# LCD.net
KiCad netlist of a schematic drawn in Altium Designer
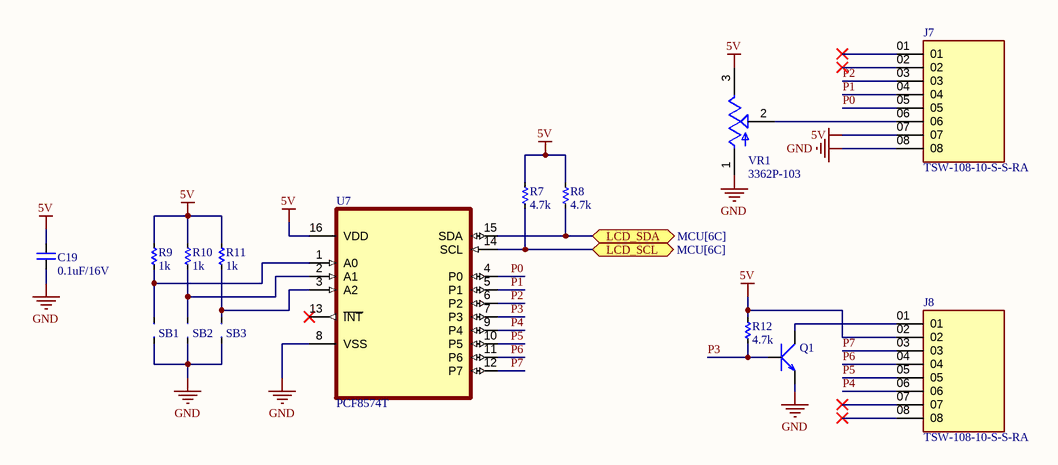
[diagram p0: LCD.SchDoc]

(export (version "E")
  (design (tool "Eeschema 10.0.6"))
  (components
    (comp (ref "C19")
      (value "0.1uF/16V")
      (footprint "CAP_C_1608X80")
      (description "CAP_Chip")
      (libsource (lib "BTL_SCHLIB") (part "CAP_SMD"))
    )
    (comp (ref "J7")
      (value "TSW-108-10-S-S-RA")
      (footprint "SAMTEC_TSW-108-10-S-S-RA")
      (description "Connector Header Through Hole, Right Angle 8 position 0.100 (2.54mm)")
      (fields (field (name "MF") "Samtec"))
      (libsource (lib "BTL_SCHLIB") (part "TSW-108-10-S-S-RA"))
    )
    (comp (ref "J8")
      (value "TSW-108-10-S-S-RA")
      (footprint "SAMTEC_TSW-108-10-S-S-RA")
      (description "Connector Header Through Hole, Right Angle 8 position 0.100 (2.54mm)")
      (fields (field (name "MF") "Samtec"))
      (libsource (lib "BTL_SCHLIB") (part "TSW-108-10-S-S-RA"))
    )
    (comp (ref "Q1")
      (value "SMD-TRANSISTORS-NPN-25V-500MW(SOT-23)")
      (footprint "SOT-23")
      (description "Bipolar (BJT) Transistor NPN 25 V 500 mA 150MHz 300 mW Surface Mount SOT-23")
      (fields (field (name "MF") "UMW") (field (name "MP") "S8050"))
      (libsource (lib "BTL_SCHLIB") (part "SMD-TRANSISTORS-NPN-25V-500MW(SOT-23)"))
    )
    (comp (ref "R7")
      (value "4.7k")
      (footprint "RES_C_1608X60")
      (description "RES")
      (libsource (lib "BTL_SCHLIB") (part "RES_SMD"))
    )
    (comp (ref "R8")
      (value "4.7k")
      (footprint "RES_C_1608X60")
      (description "RES")
      (libsource (lib "BTL_SCHLIB") (part "RES_SMD"))
    )
    (comp (ref "R9")
      (value "1k")
      (footprint "RES_C_1608X60")
      (description "RES")
      (libsource (lib "BTL_SCHLIB") (part "RES_SMD"))
    )
    (comp (ref "R10")
      (value "1k")
      (footprint "RES_C_1608X60")
      (description "RES")
      (libsource (lib "BTL_SCHLIB") (part "RES_SMD"))
    )
    (comp (ref "R11")
      (value "1k")
      (footprint "RES_C_1608X60")
      (description "RES")
      (libsource (lib "BTL_SCHLIB") (part "RES_SMD"))
    )
    (comp (ref "R12")
      (value "4.7k")
      (footprint "RES_C_1608X60")
      (description "RES")
      (libsource (lib "BTL_SCHLIB") (part "RES_SMD"))
    )
    (comp (ref "SB1")
      (value "JUMPER")
      (footprint "JUMPER_1608")
      (libsource (lib "BTL_SCHLIB") (part "JUMPER"))
    )
    (comp (ref "SB2")
      (value "JUMPER")
      (footprint "JUMPER_1608")
      (libsource (lib "BTL_SCHLIB") (part "JUMPER"))
    )
    (comp (ref "SB3")
      (value "JUMPER")
      (footprint "JUMPER_1608")
      (libsource (lib "BTL_SCHLIB") (part "JUMPER"))
    )
    (comp (ref "U7")
      (value "PCF8574T")
      (footprint "SOIC127P1032X265-16N")
      (description "I/O Expander 8 IÂ²C 100 kHz 20-SSOP")
      (fields (field (name "MF") "NXP Semiconductors"))
      (libsource (lib "BTL_SCHLIB") (part "PCF8574T"))
    )
    (comp (ref "VR1")
      (value "3362P-103")
      (footprint "TRIM_3362P-103")
      (description "10 kOhms 0.5W, 1/2W PC Pins Through Hole Trimmer Potentiometer Cermet 1 Turn Top Finger Adjustment")
      (fields (field (name "MF") "Bourns"))
      (libsource (lib "BTL_SCHLIB") (part "3362P-103"))
    )
  )
  (nets
    (net (code "1") (name "/LCD_SCL") (class "Default")
      (node (ref "R7") (pin "1") (pinfunction "1_1") (pintype "passive"))
      (node (ref "U7") (pin "14") (pinfunction "SCL_14") (pintype "input"))
    )
    (net (code "2") (name "/LCD_SDA") (class "Default")
      (node (ref "R8") (pin "1") (pinfunction "1_1") (pintype "passive"))
      (node (ref "U7") (pin "15") (pinfunction "SDA_15") (pintype "bidirectional"))
    )
    (net (code "3") (name "/P0") (class "Default")
      (node (ref "J7") (pin "05") (pinfunction "05_05") (pintype "passive"))
      (node (ref "U7") (pin "4") (pinfunction "P0_4") (pintype "bidirectional"))
    )
    (net (code "4") (name "/P1") (class "Default")
      (node (ref "J7") (pin "04") (pinfunction "04_04") (pintype "passive"))
      (node (ref "U7") (pin "5") (pinfunction "P1_5") (pintype "bidirectional"))
    )
    (net (code "5") (name "/P2") (class "Default")
      (node (ref "J7") (pin "03") (pinfunction "03_03") (pintype "passive"))
      (node (ref "U7") (pin "6") (pinfunction "P2_6") (pintype "bidirectional"))
    )
    (net (code "6") (name "/P3") (class "Default")
      (node (ref "Q1") (pin "1") (pinfunction "B_1") (pintype "passive"))
      (node (ref "R12") (pin "1") (pinfunction "1_1") (pintype "passive"))
      (node (ref "U7") (pin "7") (pinfunction "P3_7") (pintype "bidirectional"))
    )
    (net (code "7") (name "/P4") (class "Default")
      (node (ref "J8") (pin "06") (pinfunction "06_06") (pintype "passive"))
      (node (ref "U7") (pin "9") (pinfunction "P4_9") (pintype "bidirectional"))
    )
    (net (code "8") (name "/P5") (class "Default")
      (node (ref "J8") (pin "05") (pinfunction "05_05") (pintype "passive"))
      (node (ref "U7") (pin "10") (pinfunction "P5_10") (pintype "bidirectional"))
    )
    (net (code "9") (name "/P6") (class "Default")
      (node (ref "J8") (pin "04") (pinfunction "04_04") (pintype "passive"))
      (node (ref "U7") (pin "11") (pinfunction "P6_11") (pintype "bidirectional"))
    )
    (net (code "10") (name "/P7") (class "Default")
      (node (ref "J8") (pin "03") (pinfunction "03_03") (pintype "passive"))
      (node (ref "U7") (pin "12") (pinfunction "P7_12") (pintype "bidirectional"))
    )
    (net (code "11") (name "5V") (class "Default")
      (node (ref "C19") (pin "2") (pinfunction "2_2") (pintype "passive"))
      (node (ref "J7") (pin "07") (pinfunction "07_07") (pintype "passive"))
      (node (ref "J8") (pin "02") (pinfunction "02_02") (pintype "passive"))
      (node (ref "R10") (pin "2") (pinfunction "2_2") (pintype "passive"))
      (node (ref "R11") (pin "2") (pinfunction "2_2") (pintype "passive"))
      (node (ref "R12") (pin "2") (pinfunction "2_2") (pintype "passive"))
      (node (ref "R7") (pin "2") (pinfunction "2_2") (pintype "passive"))
      (node (ref "R8") (pin "2") (pinfunction "2_2") (pintype "passive"))
      (node (ref "R9") (pin "2") (pinfunction "2_2") (pintype "passive"))
      (node (ref "U7") (pin "16") (pinfunction "VDD_16") (pintype "power_in"))
      (node (ref "VR1") (pin "3") (pinfunction "CW_3") (pintype "passive"))
    )
    (net (code "12") (name "GND") (class "Default")
      (node (ref "C19") (pin "1") (pinfunction "1_1") (pintype "passive"))
      (node (ref "J7") (pin "08") (pinfunction "08_08") (pintype "passive"))
      (node (ref "Q1") (pin "2") (pinfunction "E_2") (pintype "passive"))
      (node (ref "SB1") (pin "1") (pinfunction "1_1") (pintype "passive"))
      (node (ref "SB2") (pin "1") (pinfunction "1_1") (pintype "passive"))
      (node (ref "SB3") (pin "1") (pinfunction "1_1") (pintype "passive"))
      (node (ref "U7") (pin "8") (pinfunction "VSS_8") (pintype "passive"))
      (node (ref "VR1") (pin "1") (pinfunction "CCW_1") (pintype "passive"))
    )
    (net (code "13") (name "Net-(Q1-C)") (class "Default")
      (node (ref "J8") (pin "01") (pinfunction "01_01") (pintype "passive"))
      (node (ref "Q1") (pin "3") (pinfunction "C_3") (pintype "passive"))
    )
    (net (code "14") (name "Net-(U7-A0)") (class "Default")
      (node (ref "R9") (pin "1") (pinfunction "1_1") (pintype "passive"))
      (node (ref "SB1") (pin "2") (pinfunction "2_2") (pintype "passive"))
      (node (ref "U7") (pin "1") (pinfunction "A0_1") (pintype "input"))
    )
    (net (code "15") (name "Net-(U7-A1)") (class "Default")
      (node (ref "R10") (pin "1") (pinfunction "1_1") (pintype "passive"))
      (node (ref "SB2") (pin "2") (pinfunction "2_2") (pintype "passive"))
      (node (ref "U7") (pin "2") (pinfunction "A1_2") (pintype "input"))
    )
    (net (code "16") (name "Net-(U7-A2)") (class "Default")
      (node (ref "R11") (pin "1") (pinfunction "1_1") (pintype "passive"))
      (node (ref "SB3") (pin "2") (pinfunction "2_2") (pintype "passive"))
      (node (ref "U7") (pin "3") (pinfunction "A2_3") (pintype "input"))
    )
    (net (code "17") (name "Net-(VR1-WIPER)") (class "Default")
      (node (ref "J7") (pin "06") (pinfunction "06_06") (pintype "passive"))
      (node (ref "VR1") (pin "2") (pinfunction "WIPER_2") (pintype "passive"))
    )
    (net (code "18") (name "unconnected-(J7-Pad01)") (class "Default")
      (node (ref "J7") (pin "01") (pinfunction "01_01") (pintype "passive+no_connect"))
    )
    (net (code "19") (name "unconnected-(J7-Pad02)") (class "Default")
      (node (ref "J7") (pin "02") (pinfunction "02_02") (pintype "passive+no_connect"))
    )
    (net (code "20") (name "unconnected-(J8-Pad07)") (class "Default")
      (node (ref "J8") (pin "07") (pinfunction "07_07") (pintype "passive+no_connect"))
    )
    (net (code "21") (name "unconnected-(J8-Pad08)") (class "Default")
      (node (ref "J8") (pin "08") (pinfunction "08_08") (pintype "passive+no_connect"))
    )
    (net (code "22") (name "unconnected-(U7-~{INT}-Pad13)") (class "Default")
      (node (ref "U7") (pin "13") (pinfunction "~{INT}_13") (pintype "output+no_connect"))
    )
  )
)
